# jack-o-lantern_schematic.net
KiCad netlist of a schematic drawn in EAGLE
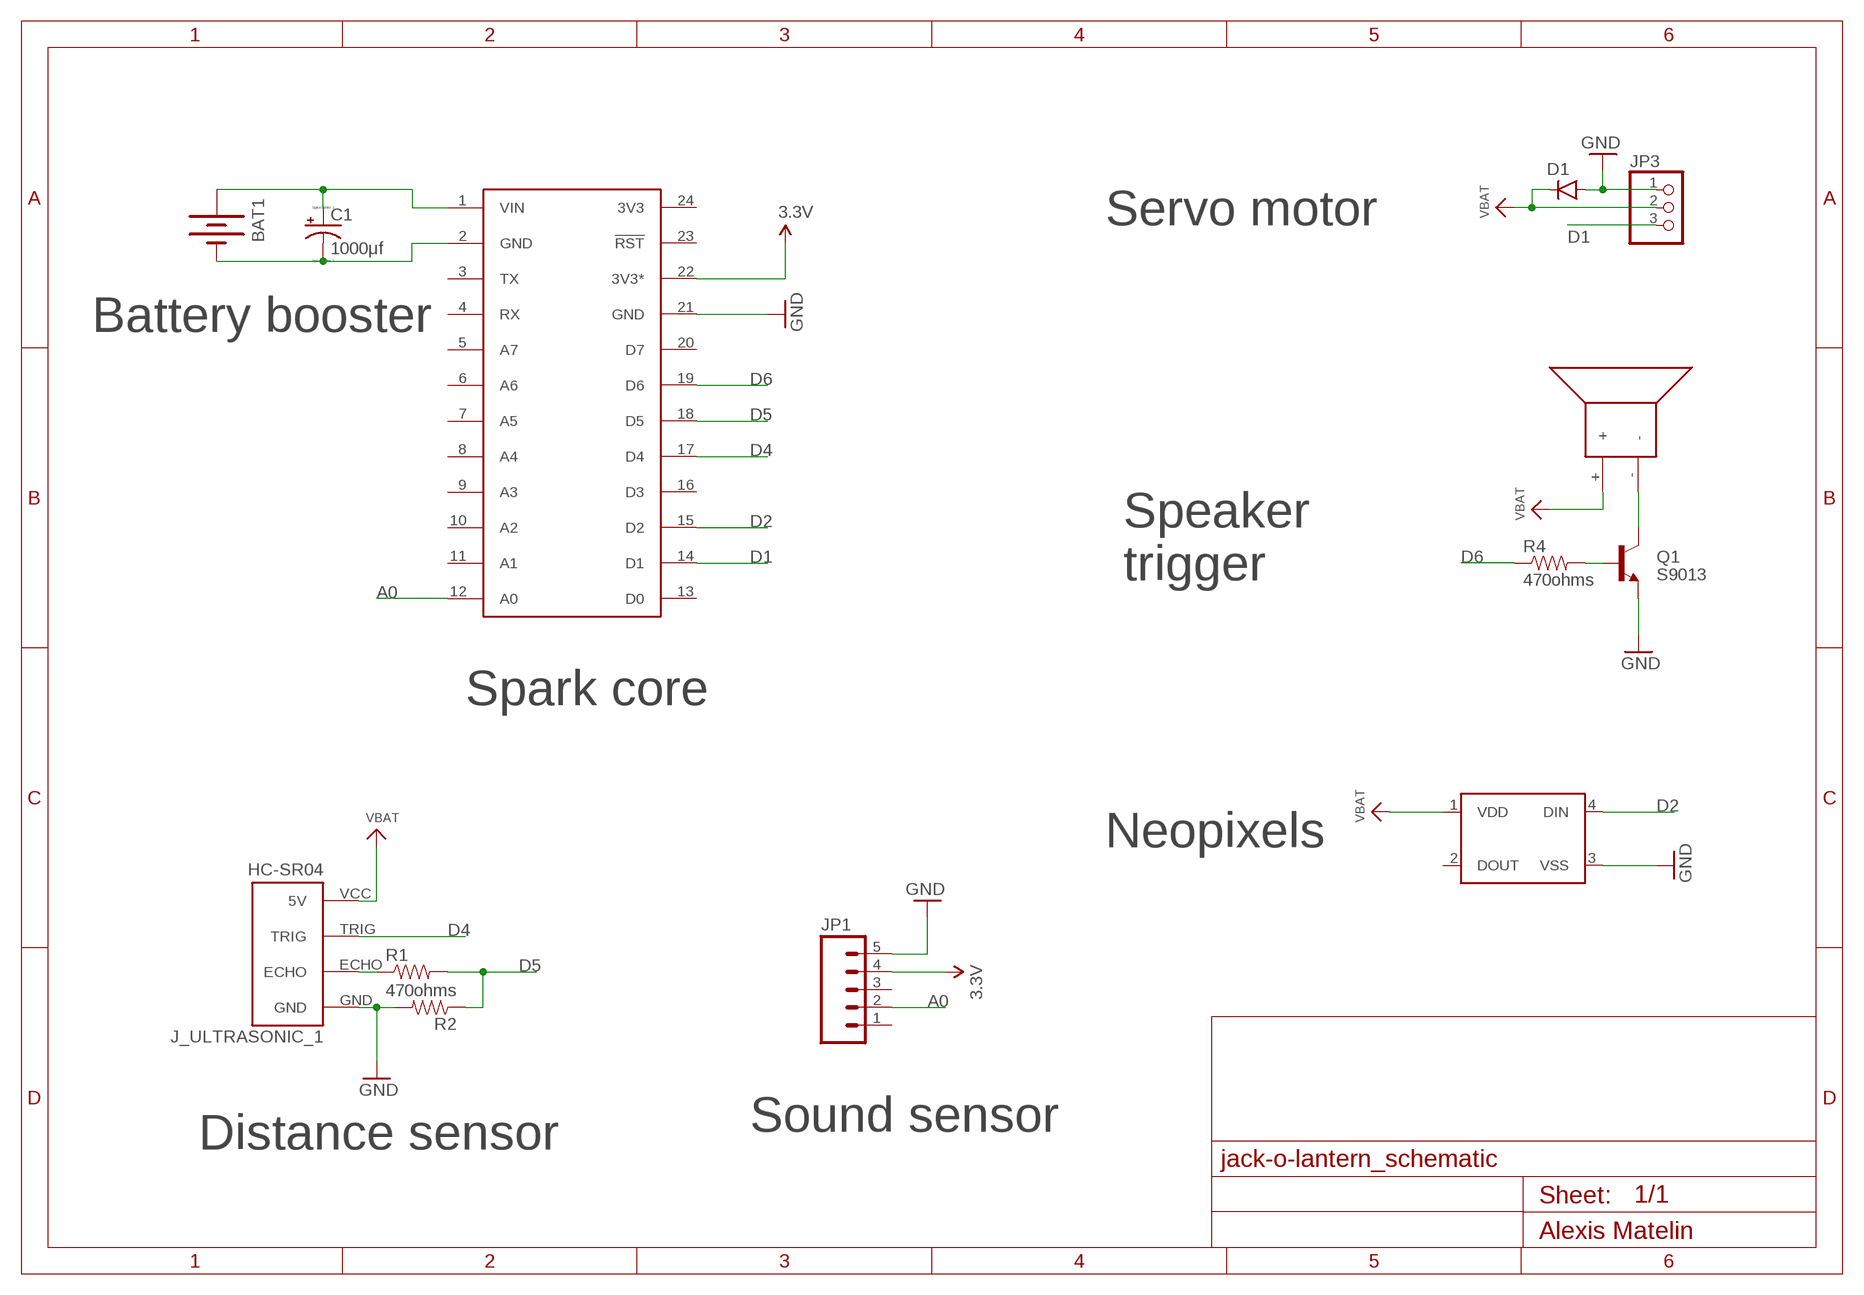
[diagram p0: schematic, sheet 1]

(export (version "E")
  (design (tool "Eeschema 10.0.6"))
  (components
    (comp (ref "BAT1")
      (value "BATTERYLIPO-TABS")
      (footprint "eagle-import:LIPO-110-TABS")
      (libsource (lib "eagle-import") (part "BATTERYLIPO-TABS"))
    )
    (comp (ref "C1")
      (value "1000μf")
      (footprint "eagle-import:E2-4")
      (libsource (lib "eagle-import") (part "CPOL-USE2-4"))
    )
    (comp (ref "D1")
      (value "DIODEPTH")
      (footprint "eagle-import:DIODE-1N4001")
      (libsource (lib "eagle-import") (part "DIODEPTH"))
    )
    (comp (ref "D3")
      (value "WS2812B")
      (footprint "eagle-import:WS2812B")
      (libsource (lib "eagle-import") (part "WS2812B"))
    )
    (comp (ref "JP1")
      (value "M05PTH")
      (footprint "eagle-import:1X05")
      (libsource (lib "eagle-import") (part "M05PTH"))
    )
    (comp (ref "JP3")
      (value "PINHD-1X3")
      (footprint "eagle-import:1X03")
      (libsource (lib "eagle-import") (part "PINHD-1X3"))
    )
    (comp (ref "J_ULTRASONIC_1")
      (value "HC-SR04")
      (footprint "eagle-import:HC-SR04_FOOTPRINT")
      (libsource (lib "eagle-import") (part "HC-SR04"))
    )
    (comp (ref "Q1")
      (value "S9013")
      (footprint "eagle-import:TO-92-AMMO")
      (libsource (lib "eagle-import") (part "TRANSISTOR_NPNBC547"))
    )
    (comp (ref "R1")
      (value "RESISTORAXIAL-0.3")
      (footprint "eagle-import:AXIAL-0.3")
      (libsource (lib "eagle-import") (part "RESISTORAXIAL-0.3"))
    )
    (comp (ref "R2")
      (value "470ohms")
      (footprint "eagle-import:AXIAL-0.3")
      (libsource (lib "eagle-import") (part "RESISTORAXIAL-0.3"))
    )
    (comp (ref "R4")
      (value "470ohms")
      (footprint "eagle-import:AXIAL-0.3")
      (libsource (lib "eagle-import") (part "RESISTORAXIAL-0.3"))
    )
    (comp (ref "SP2")
      (value "SPEAKERPCB_MOUNT")
      (footprint "eagle-import:PCB_MOUNT_SPEAKER")
      (fields (field (name "MFG") "SANCO"))
      (libsource (lib "eagle-import") (part "SPEAKERPCB_MOUNT"))
    )
    (comp (ref "U$1")
      (value "SPARK_CORECORE")
      (footprint "eagle-import:SPARK_CORE")
      (libsource (lib "eagle-import") (part "SPARK_CORECORE"))
    )
  )
  (nets
    (net (code "1") (name "/3V3") (class "Default")
      (node (ref "U$1") (pin "24") (pinfunction "3V3_24") (pintype "power_in"))
    )
    (net (code "2") (name "/A0") (class "Default")
      (node (ref "JP1") (pin "2") (pinfunction "2_2") (pintype "passive"))
      (node (ref "U$1") (pin "12") (pinfunction "A0_12") (pintype "bidirectional"))
    )
    (net (code "3") (name "/D1") (class "Default")
      (node (ref "JP3") (pin "3") (pinfunction "3_3") (pintype "passive"))
      (node (ref "U$1") (pin "14") (pinfunction "D1_14") (pintype "bidirectional"))
    )
    (net (code "4") (name "/D2") (class "Default")
      (node (ref "D3") (pin "4") (pinfunction "DIN_4") (pintype "input"))
      (node (ref "U$1") (pin "15") (pinfunction "D2_15") (pintype "bidirectional"))
    )
    (net (code "5") (name "/D4") (class "Default")
      (node (ref "J_ULTRASONIC_1") (pin "TRIG") (pinfunction "TRIG_TRIG") (pintype "bidirectional"))
      (node (ref "U$1") (pin "17") (pinfunction "D4_17") (pintype "bidirectional"))
    )
    (net (code "6") (name "/D5") (class "Default")
      (node (ref "R1") (pin "P$2") (pinfunction "2_P$2") (pintype "passive"))
      (node (ref "R2") (pin "P$1") (pinfunction "1_P$1") (pintype "passive"))
      (node (ref "U$1") (pin "18") (pinfunction "D5_18") (pintype "bidirectional"))
    )
    (net (code "7") (name "/D6") (class "Default")
      (node (ref "R4") (pin "P$1") (pinfunction "1_P$1") (pintype "passive"))
      (node (ref "U$1") (pin "19") (pinfunction "D6_19") (pintype "bidirectional"))
    )
    (net (code "8") (name "3.3V") (class "Default")
      (node (ref "JP1") (pin "4") (pinfunction "4_4") (pintype "passive"))
      (node (ref "U$1") (pin "22") (pinfunction "3V3*_22") (pintype "power_in"))
    )
    (net (code "9") (name "GND") (class "Default")
      (node (ref "D1") (pin "A") (pinfunction "A_A") (pintype "passive"))
      (node (ref "D3") (pin "3") (pinfunction "VSS_3") (pintype "power_in"))
      (node (ref "JP1") (pin "5") (pinfunction "5_5") (pintype "passive"))
      (node (ref "JP3") (pin "1") (pinfunction "1_1") (pintype "passive"))
      (node (ref "J_ULTRASONIC_1") (pin "GND") (pinfunction "GND_GND") (pintype "bidirectional"))
      (node (ref "Q1") (pin "3") (pinfunction "E_3") (pintype "passive"))
      (node (ref "R2") (pin "P$2") (pinfunction "2_P$2") (pintype "passive"))
      (node (ref "U$1") (pin "21") (pinfunction "GND_21") (pintype "power_in"))
    )
    (net (code "10") (name "Net-(BAT1-Pad-)") (class "Default")
      (node (ref "BAT1") (pin "-") (pinfunction "-_-") (pintype "power_in"))
      (node (ref "C1") (pin "-") (pinfunction "-_-") (pintype "passive"))
      (node (ref "U$1") (pin "2") (pinfunction "GND_2") (pintype "power_in"))
    )
    (net (code "11") (name "Net-(Q1-B)") (class "Default")
      (node (ref "Q1") (pin "2") (pinfunction "B_2") (pintype "passive"))
      (node (ref "R4") (pin "P$2") (pinfunction "2_P$2") (pintype "passive"))
    )
    (net (code "12") (name "Net-(Q1-C)") (class "Default")
      (node (ref "Q1") (pin "1") (pinfunction "C_1") (pintype "passive"))
      (node (ref "SP2") (pin "-") (pinfunction "-_-") (pintype "bidirectional"))
    )
    (net (code "13") (name "Net-(R1-1)") (class "Default")
      (node (ref "J_ULTRASONIC_1") (pin "ECHO") (pinfunction "ECHO_ECHO") (pintype "bidirectional"))
      (node (ref "R1") (pin "P$1") (pinfunction "1_P$1") (pintype "passive"))
    )
    (net (code "14") (name "Net-(U$1-VIN)") (class "Default")
      (node (ref "BAT1") (pin "+") (pinfunction "+_+") (pintype "power_in"))
      (node (ref "C1") (pin "+") (pinfunction "+_+") (pintype "passive"))
      (node (ref "U$1") (pin "1") (pinfunction "VIN_1") (pintype "power_in"))
    )
    (net (code "15") (name "VBAT") (class "Default")
      (node (ref "D1") (pin "C") (pinfunction "C_C") (pintype "passive"))
      (node (ref "D3") (pin "1") (pinfunction "VDD_1") (pintype "power_in"))
      (node (ref "JP3") (pin "2") (pinfunction "2_2") (pintype "passive"))
      (node (ref "J_ULTRASONIC_1") (pin "VCC") (pinfunction "5V_VCC") (pintype "bidirectional"))
      (node (ref "SP2") (pin "+") (pinfunction "+_+") (pintype "bidirectional"))
    )
    (net (code "16") (name "unconnected-(D3-DOUT-Pad2)") (class "Default")
      (node (ref "D3") (pin "2") (pinfunction "DOUT_2") (pintype "output"))
    )
    (net (code "17") (name "unconnected-(JP1-Pad1)") (class "Default")
      (node (ref "JP1") (pin "1") (pinfunction "1_1") (pintype "passive"))
    )
    (net (code "18") (name "unconnected-(JP1-Pad3)") (class "Default")
      (node (ref "JP1") (pin "3") (pinfunction "3_3") (pintype "passive"))
    )
    (net (code "19") (name "unconnected-(U$1-A1-Pad11)") (class "Default")
      (node (ref "U$1") (pin "11") (pinfunction "A1_11") (pintype "bidirectional"))
    )
    (net (code "20") (name "unconnected-(U$1-A2-Pad10)") (class "Default")
      (node (ref "U$1") (pin "10") (pinfunction "A2_10") (pintype "bidirectional"))
    )
    (net (code "21") (name "unconnected-(U$1-A3-Pad9)") (class "Default")
      (node (ref "U$1") (pin "9") (pinfunction "A3_9") (pintype "bidirectional"))
    )
    (net (code "22") (name "unconnected-(U$1-A4-Pad8)") (class "Default")
      (node (ref "U$1") (pin "8") (pinfunction "A4_8") (pintype "bidirectional"))
    )
    (net (code "23") (name "unconnected-(U$1-A5-Pad7)") (class "Default")
      (node (ref "U$1") (pin "7") (pinfunction "A5_7") (pintype "bidirectional"))
    )
    (net (code "24") (name "unconnected-(U$1-A6-Pad6)") (class "Default")
      (node (ref "U$1") (pin "6") (pinfunction "A6_6") (pintype "bidirectional"))
    )
    (net (code "25") (name "unconnected-(U$1-A7-Pad5)") (class "Default")
      (node (ref "U$1") (pin "5") (pinfunction "A7_5") (pintype "bidirectional"))
    )
    (net (code "26") (name "unconnected-(U$1-D0-Pad13)") (class "Default")
      (node (ref "U$1") (pin "13") (pinfunction "D0_13") (pintype "bidirectional"))
    )
    (net (code "27") (name "unconnected-(U$1-D3-Pad16)") (class "Default")
      (node (ref "U$1") (pin "16") (pinfunction "D3_16") (pintype "bidirectional"))
    )
    (net (code "28") (name "unconnected-(U$1-D7-Pad20)") (class "Default")
      (node (ref "U$1") (pin "20") (pinfunction "D7_20") (pintype "bidirectional"))
    )
    (net (code "29") (name "unconnected-(U$1-RX-Pad4)") (class "Default")
      (node (ref "U$1") (pin "4") (pinfunction "RX_4") (pintype "bidirectional"))
    )
    (net (code "30") (name "unconnected-(U$1-TX-Pad3)") (class "Default")
      (node (ref "U$1") (pin "3") (pinfunction "TX_3") (pintype "bidirectional"))
    )
    (net (code "31") (name "unconnected-(U$1-~{RST}-Pad23)") (class "Default")
      (node (ref "U$1") (pin "23") (pinfunction "~{RST}_23") (pintype "bidirectional"))
    )
  )
)
